# base_v2.net
KiCad netlist of a schematic drawn in EAGLE
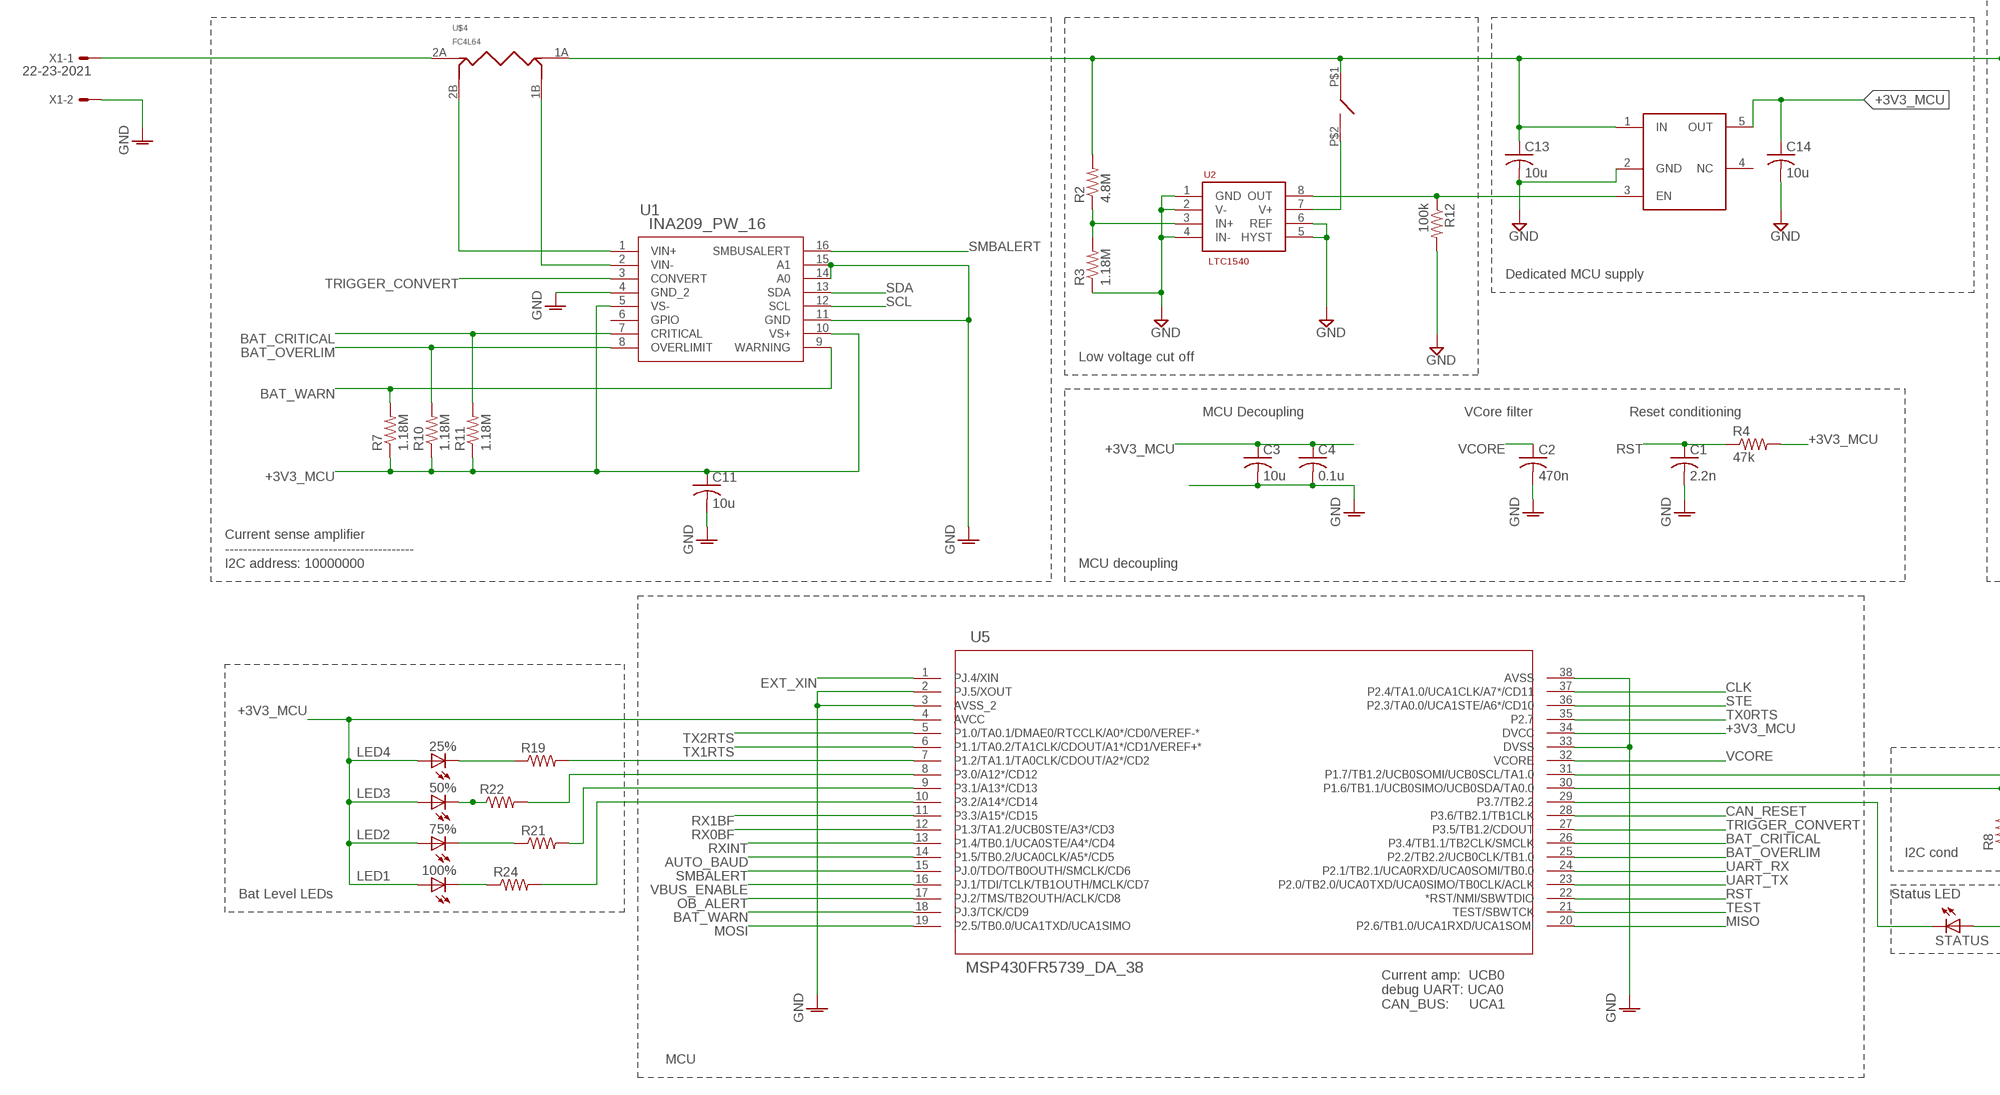
[diagram p0: schematic, sheet 1, part 1 of 2]
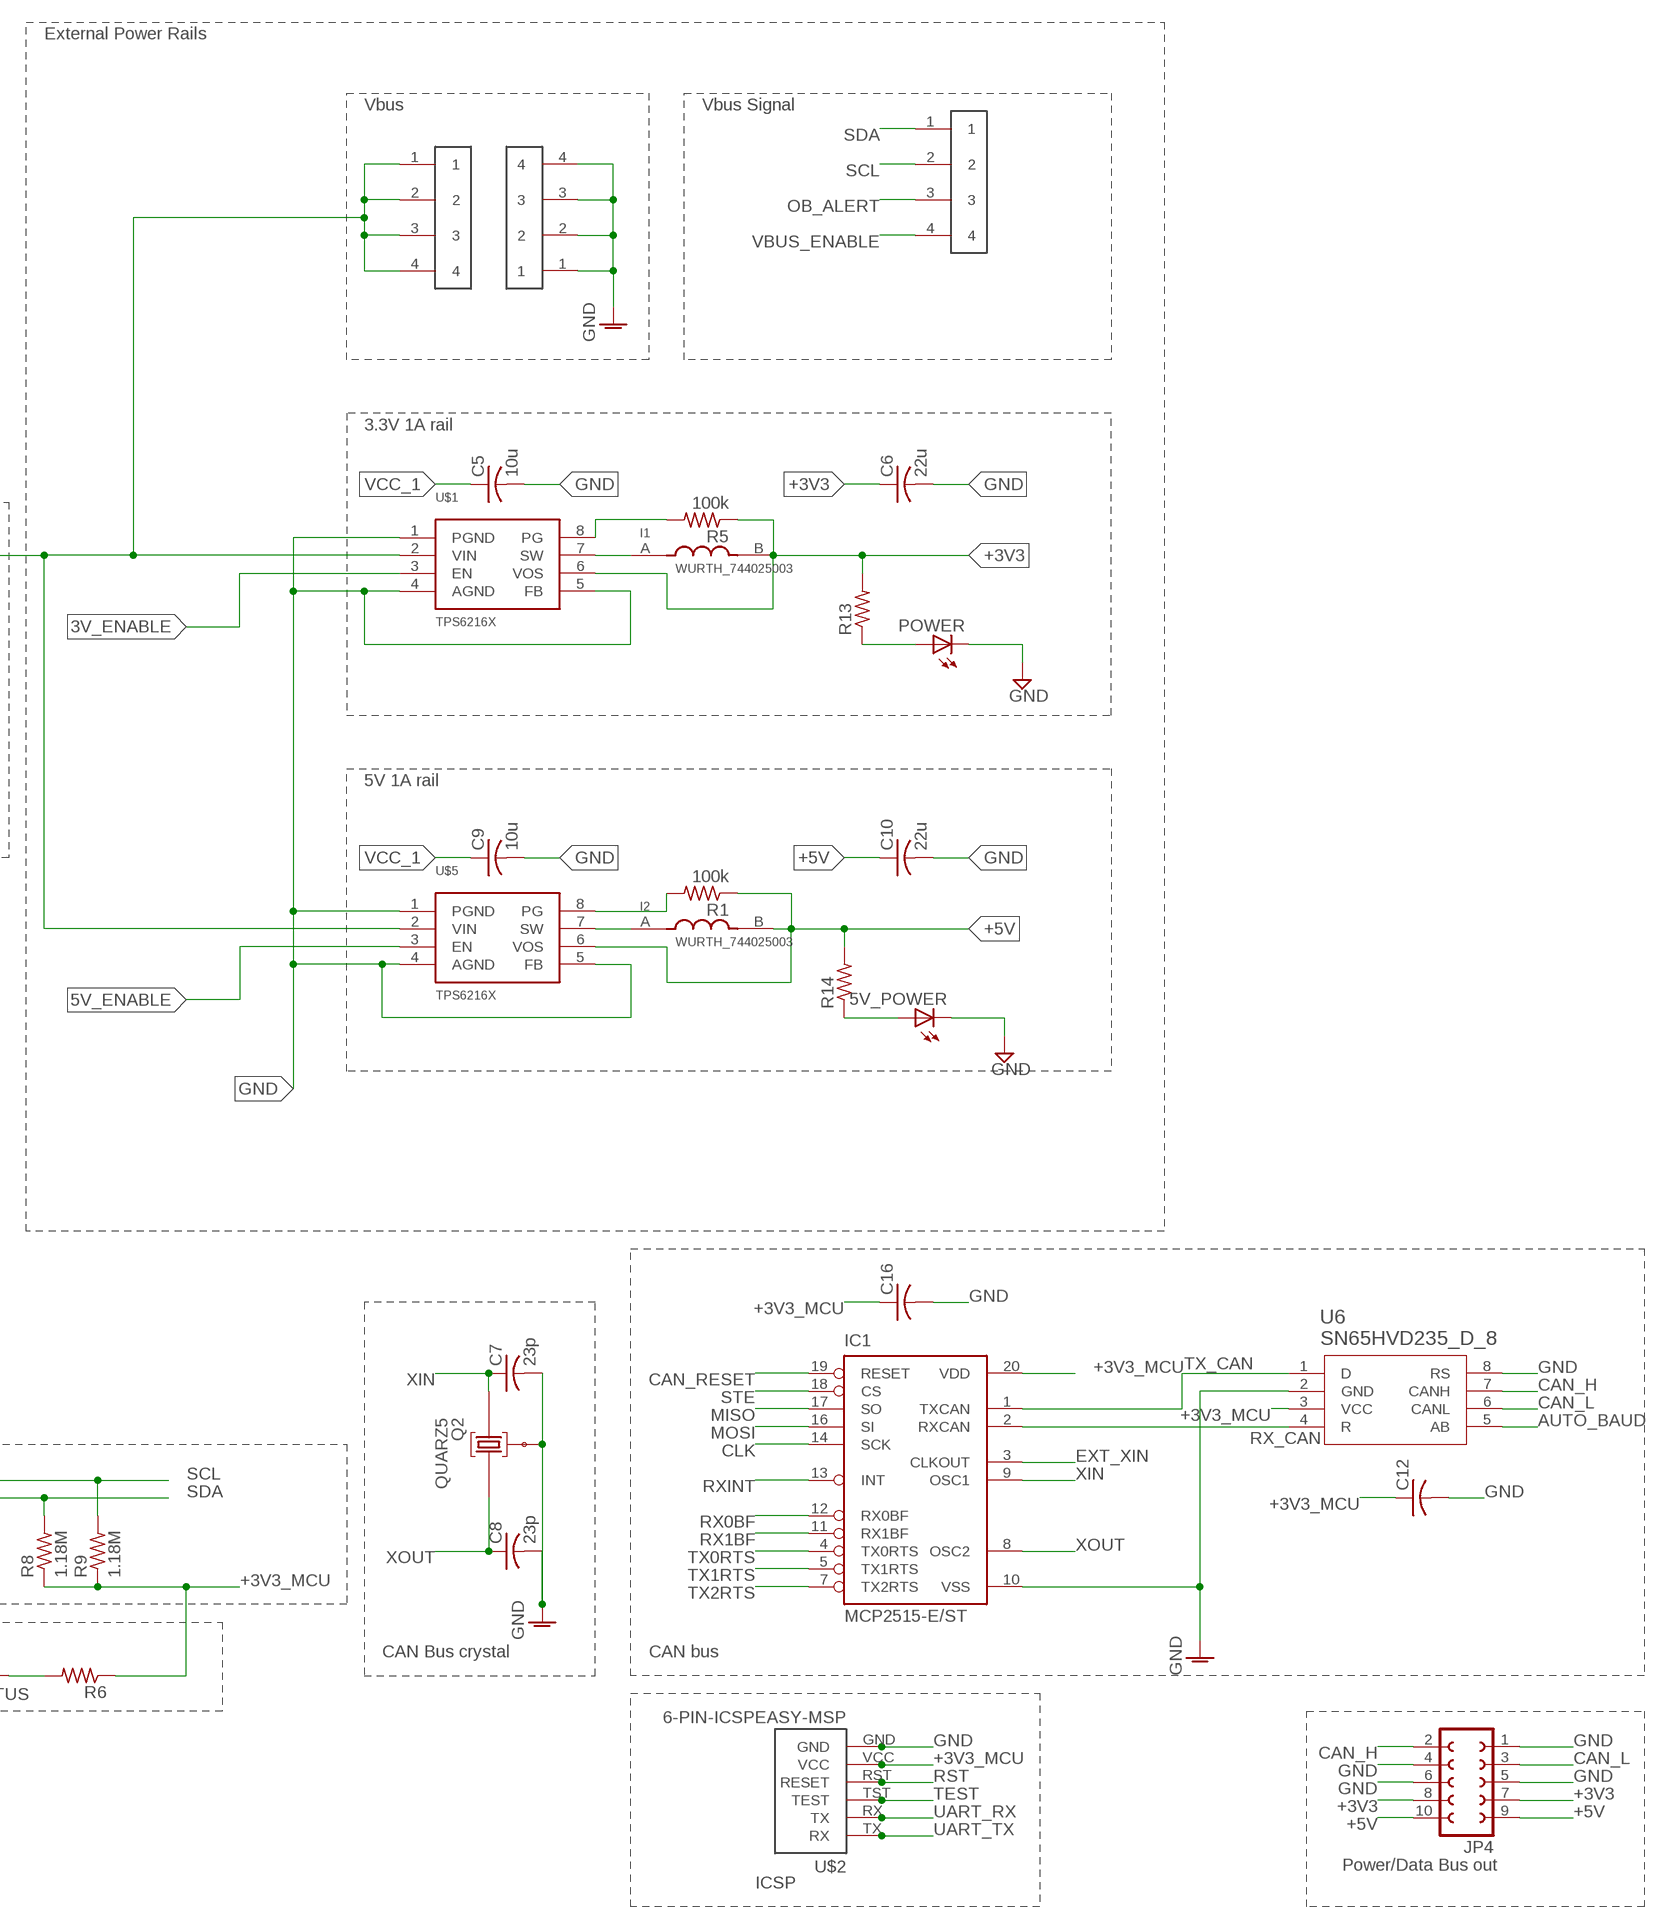
[diagram p1: schematic, sheet 1, part 2 of 2]

(export (version "E")
  (design (tool "Eeschema 10.0.6"))
  (components
    (comp (ref "5V_POWER")
      (value "LEDCHIP-LED0603")
      (footprint "eagle-import:CHIP-LED0603")
      (libsource (lib "eagle-import") (part "LEDCHIP-LED0603"))
    )
    (comp (ref "25%")
      (value "LEDCHIP-LED0603")
      (footprint "eagle-import:CHIP-LED0603")
      (libsource (lib "eagle-import") (part "LEDCHIP-LED0603"))
    )
    (comp (ref "50%")
      (value "LEDCHIP-LED0603")
      (footprint "eagle-import:CHIP-LED0603")
      (libsource (lib "eagle-import") (part "LEDCHIP-LED0603"))
    )
    (comp (ref "75%")
      (value "LEDCHIP-LED0603")
      (footprint "eagle-import:CHIP-LED0603")
      (libsource (lib "eagle-import") (part "LEDCHIP-LED0603"))
    )
    (comp (ref "100%")
      (value "LEDCHIP-LED0603")
      (footprint "eagle-import:CHIP-LED0603")
      (libsource (lib "eagle-import") (part "LEDCHIP-LED0603"))
    )
    (comp (ref "C1")
      (value "2.2n")
      (footprint "eagle-import:C1206")
      (libsource (lib "eagle-import") (part "C-USC1206"))
    )
    (comp (ref "C2")
      (value "470n")
      (footprint "eagle-import:C1206")
      (libsource (lib "eagle-import") (part "C-USC1206"))
    )
    (comp (ref "C3")
      (value "10u")
      (footprint "eagle-import:C1206")
      (libsource (lib "eagle-import") (part "C-USC1206"))
    )
    (comp (ref "C4")
      (value "0.1u")
      (footprint "eagle-import:C1206")
      (libsource (lib "eagle-import") (part "C-USC1206"))
    )
    (comp (ref "C5")
      (value "10u")
      (footprint "eagle-import:C1206")
      (libsource (lib "eagle-import") (part "C-USC1206"))
    )
    (comp (ref "C6")
      (value "22u")
      (footprint "eagle-import:C1206")
      (libsource (lib "eagle-import") (part "C-USC1206"))
    )
    (comp (ref "C7")
      (value "23p")
      (footprint "eagle-import:C1206")
      (libsource (lib "eagle-import") (part "C-USC1206"))
    )
    (comp (ref "C8")
      (value "23p")
      (footprint "eagle-import:C1206")
      (libsource (lib "eagle-import") (part "C-USC1206"))
    )
    (comp (ref "C9")
      (value "10u")
      (footprint "eagle-import:C1206")
      (libsource (lib "eagle-import") (part "C-USC1206"))
    )
    (comp (ref "C10")
      (value "22u")
      (footprint "eagle-import:C1206")
      (libsource (lib "eagle-import") (part "C-USC1206"))
    )
    (comp (ref "C11")
      (value "10u")
      (footprint "eagle-import:C1206")
      (libsource (lib "eagle-import") (part "C-USC1206"))
    )
    (comp (ref "C12")
      (value "C-USC0603")
      (footprint "eagle-import:C0603")
      (libsource (lib "eagle-import") (part "C-USC0603"))
    )
    (comp (ref "C13")
      (value "10u")
      (footprint "eagle-import:C1206")
      (libsource (lib "eagle-import") (part "C-USC1206"))
    )
    (comp (ref "C14")
      (value "10u")
      (footprint "eagle-import:C1206")
      (libsource (lib "eagle-import") (part "C-USC1206"))
    )
    (comp (ref "C16")
      (value "C-USC0603")
      (footprint "eagle-import:C0603")
      (libsource (lib "eagle-import") (part "C-USC0603"))
    )
    (comp (ref "I1")
      (value "WURTH_744025003")
      (footprint "eagle-import:INDUCTOR")
      (libsource (lib "eagle-import") (part "WURTH_744025003"))
    )
    (comp (ref "I2")
      (value "WURTH_744025003")
      (footprint "eagle-import:INDUCTOR")
      (libsource (lib "eagle-import") (part "WURTH_744025003"))
    )
    (comp (ref "IC1")
      (value "MCP2515-E/ST")
      (footprint "eagle-import:TSSOP20")
      (libsource (lib "eagle-import") (part "MCP2515-E/ST"))
    )
    (comp (ref "JP4")
      (value "FE05-2")
      (footprint "eagle-import:FE05-2")
      (libsource (lib "eagle-import") (part "FE05-2"))
    )
    (comp (ref "POWER")
      (value "LEDCHIP-LED0603")
      (footprint "eagle-import:CHIP-LED0603")
      (libsource (lib "eagle-import") (part "LEDCHIP-LED0603"))
    )
    (comp (ref "Q2")
      (value "QUARZ5")
      (footprint "eagle-import:QUARZ5")
      (libsource (lib "eagle-import") (part "QUARZ5"))
    )
    (comp (ref "R1")
      (value "100k")
      (footprint "eagle-import:R1206")
      (libsource (lib "eagle-import") (part "R-US_R1206"))
    )
    (comp (ref "R2")
      (value "4.8M")
      (footprint "eagle-import:R1206")
      (libsource (lib "eagle-import") (part "R-US_R1206"))
    )
    (comp (ref "R3")
      (value "1.18M")
      (footprint "eagle-import:R1206")
      (libsource (lib "eagle-import") (part "R-US_R1206"))
    )
    (comp (ref "R4")
      (value "47k")
      (footprint "eagle-import:R1206")
      (libsource (lib "eagle-import") (part "R-US_R1206"))
    )
    (comp (ref "R5")
      (value "100k")
      (footprint "eagle-import:R1206")
      (libsource (lib "eagle-import") (part "R-US_R1206"))
    )
    (comp (ref "R6")
      (value "R-US_R0603")
      (footprint "eagle-import:R0603")
      (libsource (lib "eagle-import") (part "R-US_R0603"))
    )
    (comp (ref "R7")
      (value "1.18M")
      (footprint "eagle-import:R0805")
      (libsource (lib "eagle-import") (part "R-US_R0805"))
    )
    (comp (ref "R8")
      (value "1.18M")
      (footprint "eagle-import:R0805")
      (libsource (lib "eagle-import") (part "R-US_R0805"))
    )
    (comp (ref "R9")
      (value "1.18M")
      (footprint "eagle-import:R0805")
      (libsource (lib "eagle-import") (part "R-US_R0805"))
    )
    (comp (ref "R10")
      (value "1.18M")
      (footprint "eagle-import:R0805")
      (libsource (lib "eagle-import") (part "R-US_R0805"))
    )
    (comp (ref "R11")
      (value "1.18M")
      (footprint "eagle-import:R0805")
      (libsource (lib "eagle-import") (part "R-US_R0805"))
    )
    (comp (ref "R12")
      (value "100k")
      (footprint "eagle-import:R1206")
      (libsource (lib "eagle-import") (part "R-US_R1206"))
    )
    (comp (ref "R13")
      (value "R-US_R0603")
      (footprint "eagle-import:R0603")
      (libsource (lib "eagle-import") (part "R-US_R0603"))
    )
    (comp (ref "R14")
      (value "R-US_R0603")
      (footprint "eagle-import:R0603")
      (libsource (lib "eagle-import") (part "R-US_R0603"))
    )
    (comp (ref "R19")
      (value "R-US_R0603")
      (footprint "eagle-import:R0603")
      (libsource (lib "eagle-import") (part "R-US_R0603"))
    )
    (comp (ref "R21")
      (value "R-US_R0603")
      (footprint "eagle-import:R0603")
      (libsource (lib "eagle-import") (part "R-US_R0603"))
    )
    (comp (ref "R22")
      (value "R-US_R0603")
      (footprint "eagle-import:R0603")
      (libsource (lib "eagle-import") (part "R-US_R0603"))
    )
    (comp (ref "R24")
      (value "R-US_R0603")
      (footprint "eagle-import:R0603")
      (libsource (lib "eagle-import") (part "R-US_R0603"))
    )
    (comp (ref "STATUS")
      (value "LEDCHIP-LED0603")
      (footprint "eagle-import:CHIP-LED0603")
      (libsource (lib "eagle-import") (part "LEDCHIP-LED0603"))
    )
    (comp (ref "U$1")
      (value "TPS6216X")
      (footprint "eagle-import:DGK-8(VSSOP)")
      (libsource (lib "eagle-import") (part "TPS6216X"))
    )
    (comp (ref "U$2")
      (value "6-PIN-ICSPEASY-MSP")
      (footprint "eagle-import:EASYMSP-6PIN")
      (libsource (lib "eagle-import") (part "6-PIN-ICSPEASY-MSP"))
    )
    (comp (ref "U$3")
      (value "1X4_HEADER")
      (footprint "eagle-import:1X4-.1HEADER")
      (libsource (lib "eagle-import") (part "1X4_HEADER"))
    )
    (comp (ref "U$4")
      (value "FC4L64")
      (footprint "eagle-import:FC4L64")
      (libsource (lib "eagle-import") (part "FC4L64"))
    )
    (comp (ref "U$5")
      (value "TPS6216X")
      (footprint "eagle-import:DGK-8(VSSOP)")
      (libsource (lib "eagle-import") (part "TPS6216X"))
    )
    (comp (ref "U$6")
      (value "TPS70930-Q1")
      (footprint "eagle-import:SOT-23")
      (libsource (lib "eagle-import") (part "TPS70930-Q1"))
    )
    (comp (ref "U$7")
      (value "A6SN")
      (footprint "eagle-import:DIP1-SMT")
      (libsource (lib "eagle-import") (part "DIP1-SMT"))
    )
    (comp (ref "U$8")
      (value "1X4_HEADER")
      (footprint "eagle-import:1X4-.1HEADER")
      (libsource (lib "eagle-import") (part "1X4_HEADER"))
    )
    (comp (ref "U$11")
      (value "1X4_HEADER")
      (footprint "eagle-import:1X4-.1HEADER")
      (libsource (lib "eagle-import") (part "1X4_HEADER"))
    )
    (comp (ref "U1")
      (value "INA209_PW_16")
      (footprint "eagle-import:PW16")
      (fields
        (field (name "GENERIC_PART_NUMBER") "INA209")
        (field (name "MANUFACTURER") "Texas Instruments")
        (field (name "MANUFACTURER_PART_NUMBER") "ina209_pw_16")
      )
      (libsource (lib "eagle-import") (part "INA209_PW_16"))
    )
    (comp (ref "U2")
      (value "LTC1540")
      (footprint "eagle-import:S8")
      (libsource (lib "eagle-import") (part "LTC1540"))
    )
    (comp (ref "U5")
      (value "MSP430FR5739_DA_38")
      (footprint "eagle-import:DA38")
      (fields
        (field (name "GENERIC_PART_NUMBER") "MSP430FR5739")
        (field (name "MANUFACTURER") "Texas Instruments")
        (field (name "MANUFACTURER_PART_NUMBER") "msp430fr5739_da_38")
      )
      (libsource (lib "eagle-import") (part "MSP430FR5739_DA_38"))
    )
    (comp (ref "U6")
      (value "SN65HVD235_D_8")
      (footprint "eagle-import:D8")
      (fields
        (field (name "GENERIC_PART_NUMBER") "SN65HVD235")
        (field (name "MANUFACTURER") "Texas Instruments")
        (field (name "MANUFACTURER_PART_NUMBER") "sn65hvd235_d_8")
      )
      (libsource (lib "eagle-import") (part "SN65HVD235_D_8"))
    )
    (comp (ref "X1")
      (value "22-23-2021")
      (footprint "eagle-import:22-23-2021")
      (fields (field (name "MF") "MOLEX"))
      (libsource (lib "eagle-import") (part "22-23-2021"))
    )
  )
  (nets
    (net (code "1") (name "+3V3") (class "Default")
      (node (ref "C6") (pin "1") (pinfunction "1_1") (pintype "passive"))
      (node (ref "I1") (pin "B") (pinfunction "B_B") (pintype "bidirectional"))
      (node (ref "JP4") (pin "7") (pinfunction "7_7") (pintype "passive"))
      (node (ref "JP4") (pin "8") (pinfunction "8_8") (pintype "passive"))
      (node (ref "R13") (pin "2") (pinfunction "2_2") (pintype "passive"))
      (node (ref "R5") (pin "1") (pinfunction "1_1") (pintype "passive"))
      (node (ref "U$1") (pin "6") (pinfunction "VOS_6") (pintype "bidirectional"))
    )
    (net (code "2") (name "+3V3_MCU") (class "Default")
      (node (ref "100%") (pin "A") (pinfunction "A_A") (pintype "passive"))
      (node (ref "25%") (pin "A") (pinfunction "A_A") (pintype "passive"))
      (node (ref "50%") (pin "A") (pinfunction "A_A") (pintype "passive"))
      (node (ref "75%") (pin "A") (pinfunction "A_A") (pintype "passive"))
      (node (ref "C11") (pin "1") (pinfunction "1_1") (pintype "passive"))
      (node (ref "C12") (pin "1") (pinfunction "1_1") (pintype "passive"))
      (node (ref "C14") (pin "1") (pinfunction "1_1") (pintype "passive"))
      (node (ref "C16") (pin "1") (pinfunction "1_1") (pintype "passive"))
      (node (ref "C3") (pin "1") (pinfunction "1_1") (pintype "passive"))
      (node (ref "C4") (pin "1") (pinfunction "1_1") (pintype "passive"))
      (node (ref "IC1") (pin "20") (pinfunction "VDD_20") (pintype "power_in"))
      (node (ref "R10") (pin "1") (pinfunction "1_1") (pintype "passive"))
      (node (ref "R11") (pin "1") (pinfunction "1_1") (pintype "passive"))
      (node (ref "R4") (pin "2") (pinfunction "2_2") (pintype "passive"))
      (node (ref "R6") (pin "1") (pinfunction "1_1") (pintype "passive"))
      (node (ref "R7") (pin "1") (pinfunction "1_1") (pintype "passive"))
      (node (ref "R8") (pin "1") (pinfunction "1_1") (pintype "passive"))
      (node (ref "R9") (pin "1") (pinfunction "1_1") (pintype "passive"))
      (node (ref "U$2") (pin "VCC") (pinfunction "VCC_VCC") (pintype "bidirectional"))
      (node (ref "U$6") (pin "5") (pinfunction "OUT_5") (pintype "bidirectional"))
      (node (ref "U1") (pin "10") (pinfunction "VS+_10") (pintype "power_in"))
      (node (ref "U1") (pin "5") (pinfunction "VS-_5") (pintype "power_in"))
      (node (ref "U5") (pin "34") (pinfunction "DVCC_34") (pintype "power_in"))
      (node (ref "U5") (pin "4") (pinfunction "AVCC_4") (pintype "power_in"))
      (node (ref "U6") (pin "3") (pinfunction "VCC_3") (pintype "power_in"))
    )
    (net (code "3") (name "+5V") (class "Default")
      (node (ref "C10") (pin "1") (pinfunction "1_1") (pintype "passive"))
      (node (ref "I2") (pin "B") (pinfunction "B_B") (pintype "bidirectional"))
      (node (ref "JP4") (pin "10") (pinfunction "10_10") (pintype "passive"))
      (node (ref "JP4") (pin "9") (pinfunction "9_9") (pintype "passive"))
      (node (ref "R1") (pin "1") (pinfunction "1_1") (pintype "passive"))
      (node (ref "R14") (pin "2") (pinfunction "2_2") (pintype "passive"))
      (node (ref "U$5") (pin "6") (pinfunction "VOS_6") (pintype "bidirectional"))
    )
    (net (code "4") (name "/AUTO_BAUD") (class "Default")
      (node (ref "U5") (pin "14") (pinfunction "P1.5/TB0.2/UCA0CLK/A5*/CD5_14") (pintype "bidirectional"))
      (node (ref "U6") (pin "5") (pinfunction "AB_5") (pintype "input"))
    )
    (net (code "5") (name "/BAT_CRITICAL") (class "Default")
      (node (ref "R11") (pin "2") (pinfunction "2_2") (pintype "passive"))
      (node (ref "U1") (pin "7") (pinfunction "CRITICAL_7") (pintype "output"))
      (node (ref "U5") (pin "26") (pinfunction "P3.4/TB1.1/TB2CLK/SMCLK_26") (pintype "bidirectional"))
    )
    (net (code "6") (name "/BAT_OVERLIM") (class "Default")
      (node (ref "R10") (pin "2") (pinfunction "2_2") (pintype "passive"))
      (node (ref "U1") (pin "8") (pinfunction "OVERLIMIT_8") (pintype "output"))
      (node (ref "U5") (pin "25") (pinfunction "P2.2/TB2.2/UCB0CLK/TB1.0_25") (pintype "bidirectional"))
    )
    (net (code "7") (name "/BAT_WARN") (class "Default")
      (node (ref "R7") (pin "2") (pinfunction "2_2") (pintype "passive"))
      (node (ref "U1") (pin "9") (pinfunction "WARNING_9") (pintype "output"))
      (node (ref "U5") (pin "18") (pinfunction "PJ.3/TCK/CD9_18") (pintype "bidirectional"))
    )
    (net (code "8") (name "/CAN_H") (class "Default")
      (node (ref "JP4") (pin "2") (pinfunction "2_2") (pintype "passive"))
      (node (ref "U6") (pin "7") (pinfunction "CANH_7") (pintype "output"))
    )
    (net (code "9") (name "/CAN_L") (class "Default")
      (node (ref "JP4") (pin "3") (pinfunction "3_3") (pintype "passive"))
      (node (ref "U6") (pin "6") (pinfunction "CANL_6") (pintype "output"))
    )
    (net (code "10") (name "/CAN_RESET") (class "Default")
      (node (ref "IC1") (pin "19") (pinfunction "RESET_19") (pintype "input"))
      (node (ref "U5") (pin "28") (pinfunction "P3.6/TB2.1/TB1CLK_28") (pintype "bidirectional"))
    )
    (net (code "11") (name "/CLK") (class "Default")
      (node (ref "IC1") (pin "14") (pinfunction "SCK_14") (pintype "input"))
      (node (ref "U5") (pin "37") (pinfunction "P2.4/TA1.0/UCA1CLK/A7*/CD11_37") (pintype "bidirectional"))
    )
    (net (code "12") (name "/EXT_XIN") (class "Default")
      (node (ref "IC1") (pin "3") (pinfunction "CLKOUT_3") (pintype "output"))
      (node (ref "U5") (pin "1") (pinfunction "PJ.4/XIN_1") (pintype "bidirectional"))
    )
    (net (code "13") (name "/LED1") (class "Default")
      (node (ref "R24") (pin "2") (pinfunction "2_2") (pintype "passive"))
      (node (ref "U5") (pin "10") (pinfunction "P3.2/A14*/CD14_10") (pintype "bidirectional"))
    )
    (net (code "14") (name "/LED2") (class "Default")
      (node (ref "R21") (pin "2") (pinfunction "2_2") (pintype "passive"))
      (node (ref "U5") (pin "9") (pinfunction "P3.1/A13*/CD13_9") (pintype "bidirectional"))
    )
    (net (code "15") (name "/LED3") (class "Default")
      (node (ref "R22") (pin "2") (pinfunction "2_2") (pintype "passive"))
      (node (ref "U5") (pin "8") (pinfunction "P3.0/A12*/CD12_8") (pintype "bidirectional"))
    )
    (net (code "16") (name "/LED4") (class "Default")
      (node (ref "R19") (pin "2") (pinfunction "2_2") (pintype "passive"))
      (node (ref "U5") (pin "7") (pinfunction "P1.2/TA1.1/TA0CLK/CDOUT/A2*/CD2_7") (pintype "bidirectional"))
    )
    (net (code "17") (name "/MISO") (class "Default")
      (node (ref "IC1") (pin "17") (pinfunction "SO_17") (pintype "output"))
      (node (ref "U5") (pin "20") (pinfunction "P2.6/TB1.0/UCA1RXD/UCA1SOMI_20") (pintype "bidirectional"))
    )
    (net (code "18") (name "/MOSI") (class "Default")
      (node (ref "IC1") (pin "16") (pinfunction "SI_16") (pintype "input"))
      (node (ref "U5") (pin "19") (pinfunction "P2.5/TB0.0/UCA1TXD/UCA1SIMO_19") (pintype "bidirectional"))
    )
    (net (code "19") (name "/OB_ALERT") (class "Default")
      (node (ref "U$8") (pin "3") (pinfunction "3_3") (pintype "bidirectional"))
      (node (ref "U5") (pin "17") (pinfunction "PJ.2/TMS/TB2OUTH/ACLK/CD8_17") (pintype "bidirectional"))
    )
    (net (code "20") (name "/RST") (class "Default")
      (node (ref "C1") (pin "1") (pinfunction "1_1") (pintype "passive"))
      (node (ref "R4") (pin "1") (pinfunction "1_1") (pintype "passive"))
      (node (ref "U$2") (pin "RST") (pinfunction "RESET_RST") (pintype "bidirectional"))
      (node (ref "U5") (pin "22") (pinfunction "*RST/NMI/SBWTDIO_22") (pintype "bidirectional"))
    )
    (net (code "21") (name "/RX0BF") (class "Default")
      (node (ref "IC1") (pin "12") (pinfunction "RX0BF_12") (pintype "output"))
      (node (ref "U5") (pin "12") (pinfunction "P1.3/TA1.2/UCB0STE/A3*/CD3_12") (pintype "bidirectional"))
    )
    (net (code "22") (name "/RX1BF") (class "Default")
      (node (ref "IC1") (pin "11") (pinfunction "RX1BF_11") (pintype "output"))
      (node (ref "U5") (pin "11") (pinfunction "P3.3/A15*/CD15_11") (pintype "bidirectional"))
    )
    (net (code "23") (name "/RXINT") (class "Default")
      (node (ref "IC1") (pin "13") (pinfunction "INT_13") (pintype "output"))
      (node (ref "U5") (pin "13") (pinfunction "P1.4/TB0.1/UCA0STE/A4*/CD4_13") (pintype "bidirectional"))
    )
    (net (code "24") (name "/RX_CAN") (class "Default")
      (node (ref "IC1") (pin "2") (pinfunction "RXCAN_2") (pintype "input"))
      (node (ref "U6") (pin "4") (pinfunction "R_4") (pintype "input"))
    )
    (net (code "25") (name "/SCL") (class "Default")
      (node (ref "R9") (pin "2") (pinfunction "2_2") (pintype "passive"))
      (node (ref "U$8") (pin "2") (pinfunction "2_2") (pintype "bidirectional"))
      (node (ref "U1") (pin "12") (pinfunction "SCL_12") (pintype "passive"))
      (node (ref "U5") (pin "31") (pinfunction "P1.7/TB1.2/UCB0SOMI/UCB0SCL/TA1.0_31") (pintype "bidirectional"))
    )
    (net (code "26") (name "/SDA") (class "Default")
      (node (ref "R8") (pin "2") (pinfunction "2_2") (pintype "passive"))
      (node (ref "U$8") (pin "1") (pinfunction "1_1") (pintype "bidirectional"))
      (node (ref "U1") (pin "13") (pinfunction "SDA_13") (pintype "passive"))
      (node (ref "U5") (pin "30") (pinfunction "P1.6/TB1.1/UCB0SIMO/UCB0SDA/TA0.0_30") (pintype "bidirectional"))
    )
    (net (code "27") (name "/SMBALERT") (class "Default")
      (node (ref "U1") (pin "16") (pinfunction "SMBUSALERT_16") (pintype "output"))
      (node (ref "U5") (pin "15") (pinfunction "PJ.0/TDO/TB0OUTH/SMCLK/CD6_15") (pintype "bidirectional"))
    )
    (net (code "28") (name "/STE") (class "Default")
      (node (ref "IC1") (pin "18") (pinfunction "CS_18") (pintype "input"))
      (node (ref "U5") (pin "36") (pinfunction "P2.3/TA0.0/UCA1STE/A6*/CD10_36") (pintype "bidirectional"))
    )
    (net (code "29") (name "/TEST") (class "Default")
      (node (ref "U$2") (pin "TST") (pinfunction "TEST_TST") (pintype "bidirectional"))
      (node (ref "U5") (pin "21") (pinfunction "TEST/SBWTCK_21") (pintype "bidirectional"))
    )
    (net (code "30") (name "/TRIGGER_CONVERT") (class "Default")
      (node (ref "U1") (pin "3") (pinfunction "CONVERT_3") (pintype "passive"))
      (node (ref "U5") (pin "27") (pinfunction "P3.5/TB1.2/CDOUT_27") (pintype "bidirectional"))
    )
    (net (code "31") (name "/TX0RTS") (class "Default")
      (node (ref "IC1") (pin "4") (pinfunction "TX0RTS_4") (pintype "input"))
      (node (ref "U5") (pin "35") (pinfunction "P2.7_35") (pintype "bidirectional"))
    )
    (net (code "32") (name "/TX1RTS") (class "Default")
      (node (ref "IC1") (pin "5") (pinfunction "TX1RTS_5") (pintype "input"))
      (node (ref "U5") (pin "6") (pinfunction "P1.1/TA0.2/TA1CLK/CDOUT/A1*/CD1/VEREF+*_6") (pintype "bidirectional"))
    )
    (net (code "33") (name "/TX2RTS") (class "Default")
      (node (ref "IC1") (pin "7") (pinfunction "TX2RTS_7") (pintype "input"))
      (node (ref "U5") (pin "5") (pinfunction "P1.0/TA0.1/DMAE0/RTCCLK/A0*/CD0/VEREF-*_5") (pintype "bidirectional"))
    )
    (net (code "34") (name "/TX_CAN") (class "Default")
      (node (ref "IC1") (pin "1") (pinfunction "TXCAN_1") (pintype "output"))
      (node (ref "U6") (pin "1") (pinfunction "D_1") (pintype "input"))
    )
    (net (code "35") (name "/UART_RX") (class "Default")
      (node (ref "U$2") (pin "RX") (pinfunction "TX_RX") (pintype "bidirectional"))
      (node (ref "U5") (pin "24") (pinfunction "P2.1/TB2.1/UCA0RXD/UCA0SOMI/TB0.0_24") (pintype "bidirectional"))
    )
    (net (code "36") (name "/UART_TX") (class "Default")
      (node (ref "U$2") (pin "TX") (pinfunction "RX_TX") (pintype "bidirectional"))
      (node (ref "U5") (pin "23") (pinfunction "P2.0/TB2.0/UCA0TXD/UCA0SIMO/TB0CLK/ACLK_23") (pintype "bidirectional"))
    )
    (net (code "37") (name "/VBUS_ENABLE") (class "Default")
      (node (ref "U$8") (pin "4") (pinfunction "4_4") (pintype "bidirectional"))
      (node (ref "U5") (pin "16") (pinfunction "PJ.1/TDI/TCLK/TB1OUTH/MCLK/CD7_16") (pintype "bidirectional"))
    )
    (net (code "38") (name "/VCORE") (class "Default")
      (node (ref "C2") (pin "1") (pinfunction "1_1") (pintype "passive"))
      (node (ref "U5") (pin "32") (pinfunction "VCORE_32") (pintype "power_in"))
    )
    (net (code "39") (name "/XIN") (class "Default")
      (node (ref "C7") (pin "1") (pinfunction "1_1") (pintype "passive"))
      (node (ref "IC1") (pin "9") (pinfunction "OSC1_9") (pintype "input"))
      (node (ref "Q2") (pin "2") (pinfunction "2_2") (pintype "passive"))
    )
    (net (code "40") (name "/XOUT") (class "Default")
      (node (ref "C8") (pin "1") (pinfunction "1_1") (pintype "passive"))
      (node (ref "IC1") (pin "8") (pinfunction "OSC2_8") (pintype "output"))
      (node (ref "Q2") (pin "1") (pinfunction "1_1") (pintype "passive"))
    )
    (net (code "41") (name "3V_ENABLE") (class "Default")
      (node (ref "U$1") (pin "3") (pinfunction "EN_3") (pintype "bidirectional"))
    )
    (net (code "42") (name "5V_ENABLE") (class "Default")
      (node (ref "U$5") (pin "3") (pinfunction "EN_3") (pintype "bidirectional"))
    )
    (net (code "43") (name "GND") (class "Default")
      (node (ref "5V_POWER") (pin "C") (pinfunction "C_C") (pintype "passive"))
      (node (ref "C1") (pin "2") (pinfunction "2_2") (pintype "passive"))
      (node (ref "C10") (pin "2") (pinfunction "2_2") (pintype "passive"))
      (node (ref "C11") (pin "2") (pinfunction "2_2") (pintype "passive"))
      (node (ref "C12") (pin "2") (pinfunction "2_2") (pintype "passive"))
      (node (ref "C13") (pin "2") (pinfunction "2_2") (pintype "passive"))
      (node (ref "C14") (pin "2") (pinfunction "2_2") (pintype "passive"))
      (node (ref "C16") (pin "2") (pinfunction "2_2") (pintype "passive"))
      (node (ref "C2") (pin "2") (pinfunction "2_2") (pintype "passive"))
      (node (ref "C3") (pin "2") (pinfunction "2_2") (pintype "passive"))
      (node (ref "C4") (pin "2") (pinfunction "2_2") (pintype "passive"))
      (node (ref "C5") (pin "2") (pinfunction "2_2") (pintype "passive"))
      (node (ref "C6") (pin "2") (pinfunction "2_2") (pintype "passive"))
      (node (ref "C7") (pin "2") (pinfunction "2_2") (pintype "passive"))
      (node (ref "C8") (pin "2") (pinfunction "2_2") (pintype "passive"))
      (node (ref "C9") (pin "2") (pinfunction "2_2") (pintype "passive"))
      (node (ref "IC1") (pin "10") (pinfunction "VSS_10") (pintype "power_in"))
      (node (ref "JP4") (pin "1") (pinfunction "1_1") (pintype "passive"))
      (node (ref "JP4") (pin "4") (pinfunction "4_4") (pintype "passive"))
      (node (ref "JP4") (pin "5") (pinfunction "5_5") (pintype "passive"))
      (node (ref "JP4") (pin "6") (pinfunction "6_6") (pintype "passive"))
      (node (ref "POWER") (pin "C") (pinfunction "C_C") (pintype "passive"))
      (node (ref "Q2") (pin "GND@0") (pinfunction "0_GND@0") (pintype "passive"))
      (node (ref "R12") (pin "2") (pinfunction "2_2") (pintype "passive"))
      (node (ref "R3") (pin "1") (pinfunction "1_1") (pintype "passive"))
      (node (ref "U$1") (pin "1") (pinfunction "PGND_1") (pintype "bidirectional"))
      (node (ref "U$1") (pin "4") (pinfunction "AGND_4") (pintype "bidirectional"))
      (node (ref "U$1") (pin "5") (pinfunction "FB_5") (pintype "bidirectional"))
      (node (ref "U$2") (pin "GND") (pinfunction "GND_GND") (pintype "bidirectional"))
      (node (ref "U$3") (pin "1") (pinfunction "1_1") (pintype "bidirectional"))
      (node (ref "U$3") (pin "2") (pinfunction "2_2") (pintype "bidirectional"))
      (node (ref "U$3") (pin "3") (pinfunction "3_3") (pintype "bidirectional"))
      (node (ref "U$3") (pin "4") (pinfunction "4_4") (pintype "bidirectional"))
      (node (ref "U$5") (pin "1") (pinfunction "PGND_1") (pintype "bidirectional"))
      (node (ref "U$5") (pin "4") (pinfunction "AGND_4") (pintype "bidirectional"))
      (node (ref "U$5") (pin "5") (pinfunction "FB_5") (pintype "bidirectional"))
      (node (ref "U$6") (pin "2") (pinfunction "GND_2") (pintype "bidirectional"))
      (node (ref "U1") (pin "11") (pinfunction "GND_11") (pintype "power_in"))
      (node (ref "U1") (pin "14") (pinfunction "A0_14") (pintype "passive"))
      (node (ref "U1") (pin "15") (pinfunction "A1_15") (pintype "passive"))
      (node (ref "U1") (pin "4") (pinfunction "GND_2_4") (pintype "power_in"))
      (node (ref "U2") (pin "1") (pinfunction "GND_1") (pintype "bidirectional"))
      (node (ref "U2") (pin "2") (pinfunction "V-_2") (pintype "bidirectional"))
      (node (ref "U2") (pin "4") (pinfunction "IN-_4") (pintype "bidirectional"))
      (node (ref "U2") (pin "5") (pinfunction "HYST_5") (pintype "bidirectional"))
      (node (ref "U2") (pin "6") (pinfunction "REF_6") (pintype "bidirectional"))
      (node (ref "U5") (pin "2") (pinfunction "PJ.5/XOUT_2") (pintype "bidirectional"))
      (node (ref "U5") (pin "3") (pinfunction "AVSS_2_3") (pintype "power_in"))
      (node (ref "U5") (pin "33") (pinfunction "DVSS_33") (pintype "power_in"))
      (node (ref "U5") (pin "38") (pinfunction "AVSS_38") (pintype "power_in"))
      (node (ref "U6") (pin "2") (pinfunction "GND_2") (pintype "power_in"))
      (node (ref "U6") (pin "8") (pinfunction "RS_8") (pintype "input"))
      (node (ref "X1") (pin "2") (pinfunction "S_2") (pintype "passive"))
    )
    (net (code "44") (name "Net-(5V_POWER-PadA)") (class "Default")
      (node (ref "5V_POWER") (pin "A") (pinfunction "A_A") (pintype "passive"))
      (node (ref "R14") (pin "1") (pinfunction "1_1") (pintype "passive"))
    )
    (net (code "45") (name "Net-(25%-PadC)") (class "Default")
      (node (ref "25%") (pin "C") (pinfunction "C_C") (pintype "passive"))
      (node (ref "R19") (pin "1") (pinfunction "1_1") (pintype "passive"))
    )
    (net (code "46") (name "Net-(50%-PadC)") (class "Default")
      (node (ref "50%") (pin "C") (pinfunction "C_C") (pintype "passive"))
      (node (ref "R22") (pin "1") (pinfunction "1_1") (pintype "passive"))
    )
    (net (code "47") (name "Net-(75%-PadC)") (class "Default")
      (node (ref "75%") (pin "C") (pinfunction "C_C") (pintype "passive"))
      (node (ref "R21") (pin "1") (pinfunction "1_1") (pintype "passive"))
    )
    (net (code "48") (name "Net-(100%-PadC)") (class "Default")
      (node (ref "100%") (pin "C") (pinfunction "C_C") (pintype "passive"))
      (node (ref "R24") (pin "1") (pinfunction "1_1") (pintype "passive"))
    )
    (net (code "49") (name "Net-(POWER-PadA)") (class "Default")
      (node (ref "POWER") (pin "A") (pinfunction "A_A") (pintype "passive"))
      (node (ref "R13") (pin "1") (pinfunction "1_1") (pintype "passive"))
    )
    (net (code "50") (name "Net-(R6-Pad2)") (class "Default")
      (node (ref "R6") (pin "2") (pinfunction "2_2") (pintype "passive"))
      (node (ref "STATUS") (pin "A") (pinfunction "A_A") (pintype "passive"))
    )
    (net (code "51") (name "Net-(U$1-PG)") (class "Default")
      (node (ref "R5") (pin "2") (pinfunction "2_2") (pintype "passive"))
      (node (ref "U$1") (pin "8") (pinfunction "PG_8") (pintype "bidirectional"))
    )
    (net (code "52") (name "Net-(U$1-SW)") (class "Default")
      (node (ref "I1") (pin "A") (pinfunction "A_A") (pintype "bidirectional"))
      (node (ref "U$1") (pin "7") (pinfunction "SW_7") (pintype "bidirectional"))
    )
    (net (code "53") (name "Net-(U$4-1A)") (class "Default")
      (node (ref "U$4") (pin "2A") (pinfunction "1A_2A") (pintype "bidirectional"))
      (node (ref "X1") (pin "1") (pinfunction "S_1") (pintype "passive"))
    )
    (net (code "54") (name "Net-(U$4-1B)") (class "Default")
      (node (ref "U$4") (pin "2B") (pinfunction "1B_2B") (pintype "bidirectional"))
      (node (ref "U1") (pin "1") (pinfunction "VIN+_1") (pintype "input"))
    )
    (net (code "55") (name "Net-(U$4-2B)") (class "Default")
      (node (ref "U$4") (pin "1B") (pinfunction "2B_1B") (pintype "bidirectional"))
      (node (ref "U1") (pin "2") (pinfunction "VIN-_2") (pintype "input"))
    )
    (net (code "56") (name "Net-(U$5-PG)") (class "Default")
      (node (ref "R1") (pin "2") (pinfunction "2_2") (pintype "passive"))
      (node (ref "U$5") (pin "8") (pinfunction "PG_8") (pintype "bidirectional"))
    )
    (net (code "57") (name "Net-(U$5-SW)") (class "Default")
      (node (ref "I2") (pin "A") (pinfunction "A_A") (pintype "bidirectional"))
      (node (ref "U$5") (pin "7") (pinfunction "SW_7") (pintype "bidirectional"))
    )
    (net (code "58") (name "Net-(U$6-EN)") (class "Default")
      (node (ref "R12") (pin "1") (pinfunction "1_1") (pintype "passive"))
      (node (ref "U$6") (pin "3") (pinfunction "EN_3") (pintype "bidirectional"))
      (node (ref "U2") (pin "8") (pinfunction "OUT_8") (pintype "bidirectional"))
    )
    (net (code "59") (name "Net-(U$7-2)") (class "Default")
      (node (ref "U$7") (pin "P$2") (pinfunction "2_P$2") (pintype "bidirectional"))
      (node (ref "U2") (pin "7") (pinfunction "V+_7") (pintype "bidirectional"))
    )
    (net (code "60") (name "Net-(U2-IN+)") (class "Default")
      (node (ref "R2") (pin "1") (pinfunction "1_1") (pintype "passive"))
      (node (ref "R3") (pin "2") (pinfunction "2_2") (pintype "passive"))
      (node (ref "U2") (pin "3") (pinfunction "IN+_3") (pintype "bidirectional"))
    )
    (net (code "61") (name "Net-(U5-P3.7{slash}TB2.2)") (class "Default")
      (node (ref "STATUS") (pin "C") (pinfunction "C_C") (pintype "passive"))
      (node (ref "U5") (pin "29") (pinfunction "P3.7/TB2.2_29") (pintype "bidirectional"))
    )
    (net (code "62") (name "VCC_1") (class "Default")
      (node (ref "C13") (pin "1") (pinfunction "1_1") (pintype "passive"))
      (node (ref "C5") (pin "1") (pinfunction "1_1") (pintype "passive"))
      (node (ref "C9") (pin "1") (pinfunction "1_1") (pintype "passive"))
      (node (ref "R2") (pin "2") (pinfunction "2_2") (pintype "passive"))
      (node (ref "U$1") (pin "2") (pinfunction "VIN_2") (pintype "bidirectional"))
      (node (ref "U$11") (pin "1") (pinfunction "1_1") (pintype "bidirectional"))
      (node (ref "U$11") (pin "2") (pinfunction "2_2") (pintype "bidirectional"))
      (node (ref "U$11") (pin "3") (pinfunction "3_3") (pintype "bidirectional"))
      (node (ref "U$11") (pin "4") (pinfunction "4_4") (pintype "bidirectional"))
      (node (ref "U$4") (pin "1A") (pinfunction "2A_1A") (pintype "bidirectional"))
      (node (ref "U$5") (pin "2") (pinfunction "VIN_2") (pintype "bidirectional"))
      (node (ref "U$6") (pin "1") (pinfunction "IN_1") (pintype "bidirectional"))
      (node (ref "U$7") (pin "P$1") (pinfunction "1_P$1") (pintype "bidirectional"))
    )
    (net (code "63") (name "unconnected-(U$6-NC-Pad4)") (class "Default")
      (node (ref "U$6") (pin "4") (pinfunction "NC_4") (pintype "bidirectional"))
    )
    (net (code "64") (name "unconnected-(U1-GPIO-Pad6)") (class "Default")
      (node (ref "U1") (pin "6") (pinfunction "GPIO_6") (pintype "passive"))
    )
  )
)
